# motorboard.net
KiCad netlist of a schematic drawn in EAGLE
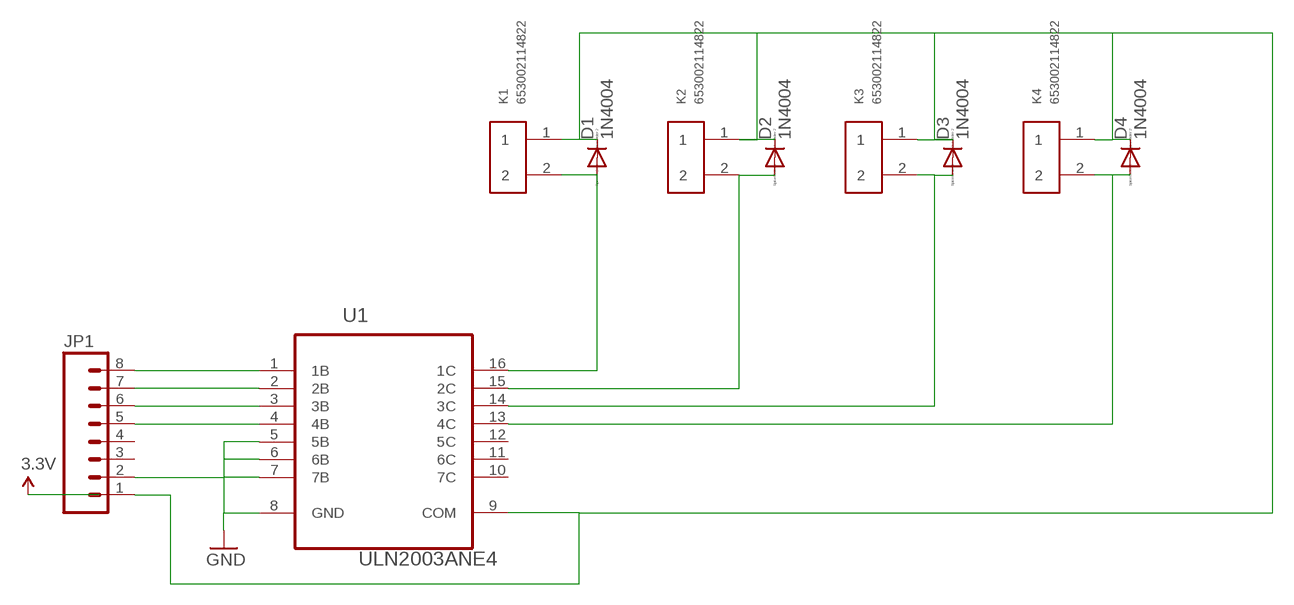
[diagram p0: schematic, sheet 1]

(export (version "E")
  (design (tool "Eeschema 10.0.6"))
  (components
    (comp (ref "D1")
      (value "1N4004")
      (footprint "eagle-import:DO41-10")
      (fields (field (name "MF") "NTE ELECTRONICS"))
      (libsource (lib "eagle-import") (part "1N4004"))
    )
    (comp (ref "D2")
      (value "1N4004")
      (footprint "eagle-import:DO41-10")
      (fields (field (name "MF") "NTE ELECTRONICS"))
      (libsource (lib "eagle-import") (part "1N4004"))
    )
    (comp (ref "D3")
      (value "1N4004")
      (footprint "eagle-import:DO41-10")
      (fields (field (name "MF") "NTE ELECTRONICS"))
      (libsource (lib "eagle-import") (part "1N4004"))
    )
    (comp (ref "D4")
      (value "1N4004")
      (footprint "eagle-import:DO41-10")
      (fields (field (name "MF") "NTE ELECTRONICS"))
      (libsource (lib "eagle-import") (part "1N4004"))
    )
    (comp (ref "JP1")
      (value "M08NO_SILK_FEMALE_PTH")
      (footprint "eagle-import:1X08_NO_SILK")
      (libsource (lib "eagle-import") (part "M08NO_SILK_FEMALE_PTH"))
    )
    (comp (ref "K1")
      (value "653002114822")
      (footprint "eagle-import:653002114822")
      (libsource (lib "eagle-import") (part "653002114822"))
    )
    (comp (ref "K2")
      (value "653002114822")
      (footprint "eagle-import:653002114822")
      (libsource (lib "eagle-import") (part "653002114822"))
    )
    (comp (ref "K3")
      (value "653002114822")
      (footprint "eagle-import:653002114822")
      (libsource (lib "eagle-import") (part "653002114822"))
    )
    (comp (ref "K4")
      (value "653002114822")
      (footprint "eagle-import:653002114822")
      (libsource (lib "eagle-import") (part "653002114822"))
    )
    (comp (ref "U1")
      (value "ULN2003ANE4")
      (footprint "eagle-import:DIP254P762X508-16")
      (libsource (lib "eagle-import") (part "ULN2003ANE4"))
    )
  )
  (nets
    (net (code "2") (name "GND") (class "Default")
      (node (ref "JP1") (pin "2") (pinfunction "2_2") (pintype "passive"))
      (node (ref "U1") (pin "5") (pinfunction "5B_5") (pintype "input"))
      (node (ref "U1") (pin "6") (pinfunction "6B_6") (pintype "input"))
      (node (ref "U1") (pin "7") (pinfunction "7B_7") (pintype "input"))
      (node (ref "U1") (pin "8") (pinfunction "GND_8") (pintype "passive"))
    )
    (net (code "3") (name "Net-(U1-1B)") (class "Default")
      (node (ref "JP1") (pin "8") (pinfunction "8_8") (pintype "passive"))
      (node (ref "U1") (pin "1") (pinfunction "1B_1") (pintype "input"))
    )
    (net (code "4") (name "Net-(U1-1C)") (class "Default")
      (node (ref "D1") (pin "A") (pinfunction "A_A") (pintype "passive"))
      (node (ref "K1") (pin "2") (pinfunction "2_2") (pintype "bidirectional"))
      (node (ref "U1") (pin "16") (pinfunction "1C_16") (pintype "output"))
    )
    (net (code "5") (name "Net-(U1-2B)") (class "Default")
      (node (ref "JP1") (pin "7") (pinfunction "7_7") (pintype "passive"))
      (node (ref "U1") (pin "2") (pinfunction "2B_2") (pintype "input"))
    )
    (net (code "6") (name "Net-(U1-2C)") (class "Default")
      (node (ref "D2") (pin "A") (pinfunction "A_A") (pintype "passive"))
      (node (ref "K2") (pin "2") (pinfunction "2_2") (pintype "bidirectional"))
      (node (ref "U1") (pin "15") (pinfunction "2C_15") (pintype "output"))
    )
    (net (code "7") (name "Net-(U1-3B)") (class "Default")
      (node (ref "JP1") (pin "6") (pinfunction "6_6") (pintype "passive"))
      (node (ref "U1") (pin "3") (pinfunction "3B_3") (pintype "input"))
    )
    (net (code "8") (name "Net-(U1-3C)") (class "Default")
      (node (ref "D3") (pin "A") (pinfunction "A_A") (pintype "passive"))
      (node (ref "K3") (pin "2") (pinfunction "2_2") (pintype "bidirectional"))
      (node (ref "U1") (pin "14") (pinfunction "3C_14") (pintype "output"))
    )
    (net (code "9") (name "Net-(U1-4B)") (class "Default")
      (node (ref "JP1") (pin "5") (pinfunction "5_5") (pintype "passive"))
      (node (ref "U1") (pin "4") (pinfunction "4B_4") (pintype "input"))
    )
    (net (code "10") (name "Net-(U1-4C)") (class "Default")
      (node (ref "D4") (pin "A") (pinfunction "A_A") (pintype "passive"))
      (node (ref "K4") (pin "2") (pinfunction "2_2") (pintype "bidirectional"))
      (node (ref "U1") (pin "13") (pinfunction "4C_13") (pintype "output"))
    )
    (net (code "11") (name "Net-(U1-COM)") (class "Default")
      (node (ref "D1") (pin "C") (pinfunction "C_C") (pintype "passive"))
      (node (ref "D2") (pin "C") (pinfunction "C_C") (pintype "passive"))
      (node (ref "D3") (pin "C") (pinfunction "C_C") (pintype "passive"))
      (node (ref "D4") (pin "C") (pinfunction "C_C") (pintype "passive"))
      (node (ref "JP1") (pin "1") (pinfunction "1_1") (pintype "passive"))
      (node (ref "K1") (pin "1") (pinfunction "1_1") (pintype "bidirectional"))
      (node (ref "K2") (pin "1") (pinfunction "1_1") (pintype "bidirectional"))
      (node (ref "K3") (pin "1") (pinfunction "1_1") (pintype "bidirectional"))
      (node (ref "K4") (pin "1") (pinfunction "1_1") (pintype "bidirectional"))
      (node (ref "U1") (pin "9") (pinfunction "COM_9") (pintype "output"))
    )
    (net (code "12") (name "unconnected-(JP1-Pad3)") (class "Default")
      (node (ref "JP1") (pin "3") (pinfunction "3_3") (pintype "passive"))
    )
    (net (code "13") (name "unconnected-(JP1-Pad4)") (class "Default")
      (node (ref "JP1") (pin "4") (pinfunction "4_4") (pintype "passive"))
    )
    (net (code "14") (name "unconnected-(U1-5C-Pad12)") (class "Default")
      (node (ref "U1") (pin "12") (pinfunction "5C_12") (pintype "output"))
    )
    (net (code "15") (name "unconnected-(U1-6C-Pad11)") (class "Default")
      (node (ref "U1") (pin "11") (pinfunction "6C_11") (pintype "output"))
    )
    (net (code "16") (name "unconnected-(U1-7C-Pad10)") (class "Default")
      (node (ref "U1") (pin "10") (pinfunction "7C_10") (pintype "output"))
    )
  )
)
